# 9-10-00222-7_Sheet1_REV02_062018.net
KiCad netlist of a schematic drawn in Altium Designer
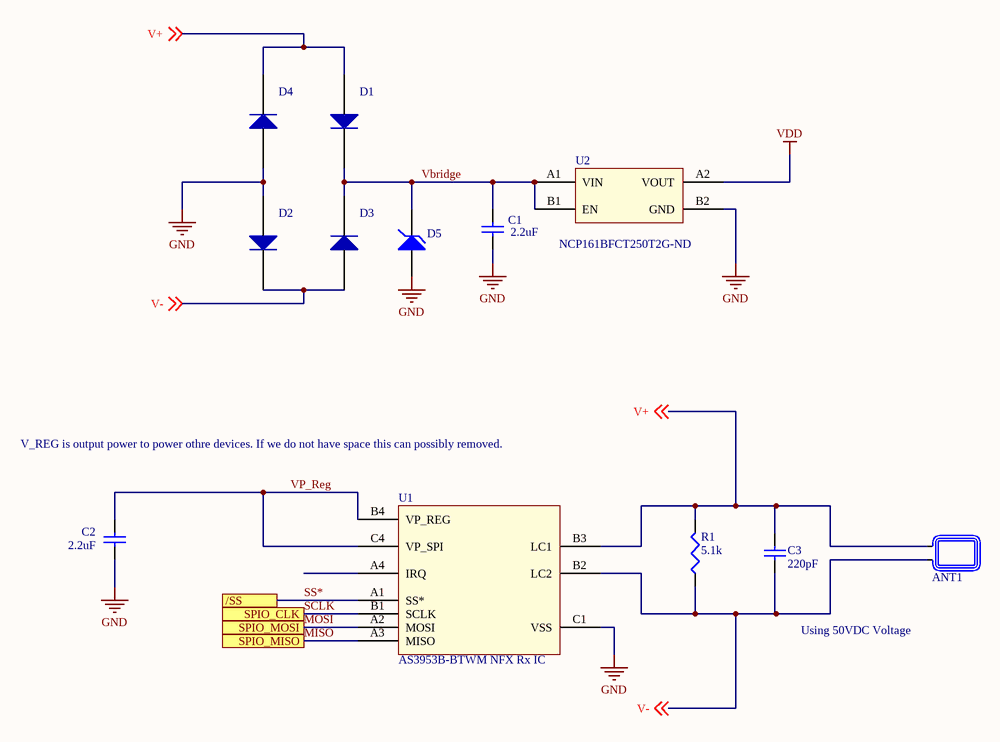
[diagram p0: 9-10-00222-7_Sheet1_REV02_062018.SchDoc]

(export (version "E")
  (design (tool "Eeschema 10.0.6"))
  (components
    (comp (ref "ANT1")
      (value "~")
      (footprint "NFC ANTENNA MOUNT - SMALL")
      (description "NFC Antenna")
      (libsource (lib "ZPower") (part "NFC_Antenna"))
    )
    (comp (ref "C1")
      (value "2.2uF")
      (footprint "CAPC0603X03L(0201)")
      (description "CAP CER 2.2UF 6.3V X5R 0201")
      (fields
        (field (name "MANUFACTURER PART NUMBER") "GRM033R60J225ME47D")
        (field (name "TOLERANCE") "20%")
        (field (name "PUBLISHER") "Altium Limited")
      )
      (libsource (lib "Miscellaneous Devices") (part "Cap Semi"))
    )
    (comp (ref "C2")
      (value "2.2uF")
      (footprint "CAPC0603X03L(0201)")
      (description "CAP CER 2.2UF 6.3V X5R 0201")
      (fields
        (field (name "MANUFACTURER PART NUMBER") "GRM033R60J225ME47D")
        (field (name "TOLERANCE") "20%")
        (field (name "PUBLISHER") "Altium Limited")
      )
      (libsource (lib "Miscellaneous Devices") (part "Cap Semi"))
    )
    (comp (ref "C3")
      (value "220pF")
      (footprint "CAPC0603X03L(0201)")
      (description "Capacitor")
      (fields
        (field (name "MANUFACTURER") "Murata")
        (field (name "MANUFACTURER PART NUMBER") "GRM0335C1H221JA01D")
      )
      (libsource (lib "ZPower") (part "Cap"))
    )
    (comp (ref "D1")
      (value "497-15253-1-ND")
      (footprint "BAT30F4")
      (description "DIODE SCHOTTKY")
      (fields
        (field (name "MANUFACTURER") "STMicroelectronics")
        (field (name "MANUFACTURER PART NUMBER") "BAT30F4")
      )
      (libsource (lib "Wireless Z601") (part "BAT30F4"))
    )
    (comp (ref "D2")
      (value "497-15253-1-ND")
      (footprint "BAT30F4")
      (description "DIODE SCHOTTKY")
      (fields
        (field (name "MANUFACTURER") "STMicroelectronics")
        (field (name "MANUFACTURER PART NUMBER") "BAT30F4")
      )
      (libsource (lib "Wireless Z601") (part "BAT30F4"))
    )
    (comp (ref "D3")
      (value "497-15253-1-ND")
      (footprint "BAT30F4")
      (description "DIODE SCHOTTKY")
      (fields
        (field (name "MANUFACTURER") "STMicroelectronics")
        (field (name "MANUFACTURER PART NUMBER") "BAT30F4")
      )
      (libsource (lib "Wireless Z601") (part "BAT30F4"))
    )
    (comp (ref "D4")
      (value "497-15253-1-ND")
      (footprint "BAT30F4")
      (description "DIODE SCHOTTKY")
      (fields
        (field (name "MANUFACTURER") "STMicroelectronics")
        (field (name "MANUFACTURER PART NUMBER") "BAT30F4")
      )
      (libsource (lib "Wireless Z601") (part "BAT30F4"))
    )
    (comp (ref "D5")
      (value "GDZ4V7LP3-7DICT-ND")
      (footprint "DFN35P61X30-2N")
      (description "DIODE ZENER 4.7V 250MW 2DFN")
      (fields (field (name "MANUFACTURER") "Diodes") (field (name "MANUFACTURER PART NUMBER") "GDZ4V7LP3-7"))
      (libsource (lib "ZPower") (part "GDZ4V7LP3-7"))
    )
    (comp (ref "R1")
      (value "5.1k")
      (footprint "RES1005X06L (0402 Imperial)")
      (description "RES SMD 5.1KOHM 0.25% 1/16W 0402")
      (fields
        (field (name "MANUFACTURER") "Panasonic")
        (field (name "MANUFACTURER PART NUMBER") "ERA-2ARC512X")
      )
      (libsource (lib "ZPower") (part "Resistor"))
    )
    (comp (ref "U1")
      (value "AS3953B-BTWM NFX Rx IC")
      (footprint "10-WLCSP")
      (description "IC NFC INTERFACE 14443A LEVEL4")
      (fields
        (field (name "MANUFACTURER") "austriamicrosystems (ams)")
        (field (name "MANUFACTURER PART NUMBER") "AS3953B-BTWM")
      )
      (libsource (lib "ZPower") (part "AS3953A_WLCSP"))
    )
    (comp (ref "U2")
      (value "2.5V LDO 450mA non-active")
      (footprint "BGA4x2")
      (description "LDO Voltage Regulators CSP LDO 450MA NON-ACTIVE")
      (fields
        (field (name "MANUFACTURER") "OnSemi")
        (field (name "MANUFACTURER PART NUMBER") "LDBL20D-25R")
        (field (name "SUPPLIER PART NUMBER 1") "NCP161BFCT250T2G-ND")
      )
      (libsource (lib "Wireless Z601") (part "NCP161BFCT250T2G"))
    )
  )
  (nets
    (net (code "1") (name "/MISO") (class "Default")
      (node (ref "U1") (pin "A3") (pinfunction "MISO_A3") (pintype "passive"))
    )
    (net (code "2") (name "/MOSI") (class "Default")
      (node (ref "U1") (pin "A2") (pinfunction "MOSI_A2") (pintype "passive"))
    )
    (net (code "3") (name "/SCLK") (class "Default")
      (node (ref "U1") (pin "B1") (pinfunction "SCLK_B1") (pintype "passive"))
    )
    (net (code "4") (name "/SS*") (class "Default")
      (node (ref "U1") (pin "A1") (pinfunction "SS*_A1") (pintype "passive"))
    )
    (net (code "5") (name "/VP_Reg") (class "Default")
      (node (ref "C2") (pin "2") (pinfunction "2_2") (pintype "passive"))
      (node (ref "U1") (pin "B4") (pinfunction "VP_REG_B4") (pintype "passive"))
      (node (ref "U1") (pin "C4") (pinfunction "VP_SPI_C4") (pintype "passive"))
    )
    (net (code "6") (name "/Vbridge") (class "Default")
      (node (ref "C1") (pin "2") (pinfunction "2_2") (pintype "passive"))
      (node (ref "D1") (pin "1") (pinfunction "1_1") (pintype "passive"))
      (node (ref "D3") (pin "1") (pinfunction "1_1") (pintype "passive"))
      (node (ref "D5") (pin "1") (pinfunction "Cathode_1") (pintype "passive"))
      (node (ref "U2") (pin "A1") (pinfunction "VIN_A1") (pintype "passive"))
      (node (ref "U2") (pin "B1") (pinfunction "EN_B1") (pintype "passive"))
    )
    (net (code "7") (name "GND") (class "Default")
      (node (ref "C1") (pin "1") (pinfunction "1_1") (pintype "passive"))
      (node (ref "C2") (pin "1") (pinfunction "1_1") (pintype "passive"))
      (node (ref "D2") (pin "2") (pinfunction "2_2") (pintype "passive"))
      (node (ref "D4") (pin "2") (pinfunction "2_2") (pintype "passive"))
      (node (ref "D5") (pin "2") (pinfunction "Anode_2") (pintype "passive"))
      (node (ref "U1") (pin "C1") (pinfunction "VSS_C1") (pintype "passive"))
      (node (ref "U2") (pin "B2") (pinfunction "GND_B2") (pintype "passive"))
    )
    (net (code "8") (name "V+") (class "Default")
      (node (ref "ANT1") (pin "1") (pinfunction "1_1") (pintype "passive"))
      (node (ref "C3") (pin "1") (pinfunction "1_1") (pintype "passive"))
      (node (ref "D1") (pin "2") (pinfunction "2_2") (pintype "passive"))
      (node (ref "D4") (pin "1") (pinfunction "1_1") (pintype "passive"))
      (node (ref "R1") (pin "1") (pinfunction "1_1") (pintype "passive"))
      (node (ref "U1") (pin "B3") (pinfunction "LC1_B3") (pintype "passive"))
    )
    (net (code "9") (name "V-") (class "Default")
      (node (ref "ANT1") (pin "2") (pinfunction "2_2") (pintype "passive"))
      (node (ref "C3") (pin "2") (pinfunction "2_2") (pintype "passive"))
      (node (ref "D2") (pin "1") (pinfunction "1_1") (pintype "passive"))
      (node (ref "D3") (pin "2") (pinfunction "2_2") (pintype "passive"))
      (node (ref "R1") (pin "2") (pinfunction "2_2") (pintype "passive"))
      (node (ref "U1") (pin "B2") (pinfunction "LC2_B2") (pintype "passive"))
    )
    (net (code "10") (name "VDD") (class "Default")
      (node (ref "U2") (pin "A2") (pinfunction "VOUT_A2") (pintype "passive"))
    )
    (net (code "11") (name "unconnected-(U1-IRQ-PadA4)") (class "Default")
      (node (ref "U1") (pin "A4") (pinfunction "IRQ_A4") (pintype "passive"))
    )
  )
)
